# MCU025A_F280049C_Device.net
KiCad netlist of a schematic drawn in Altium Designer
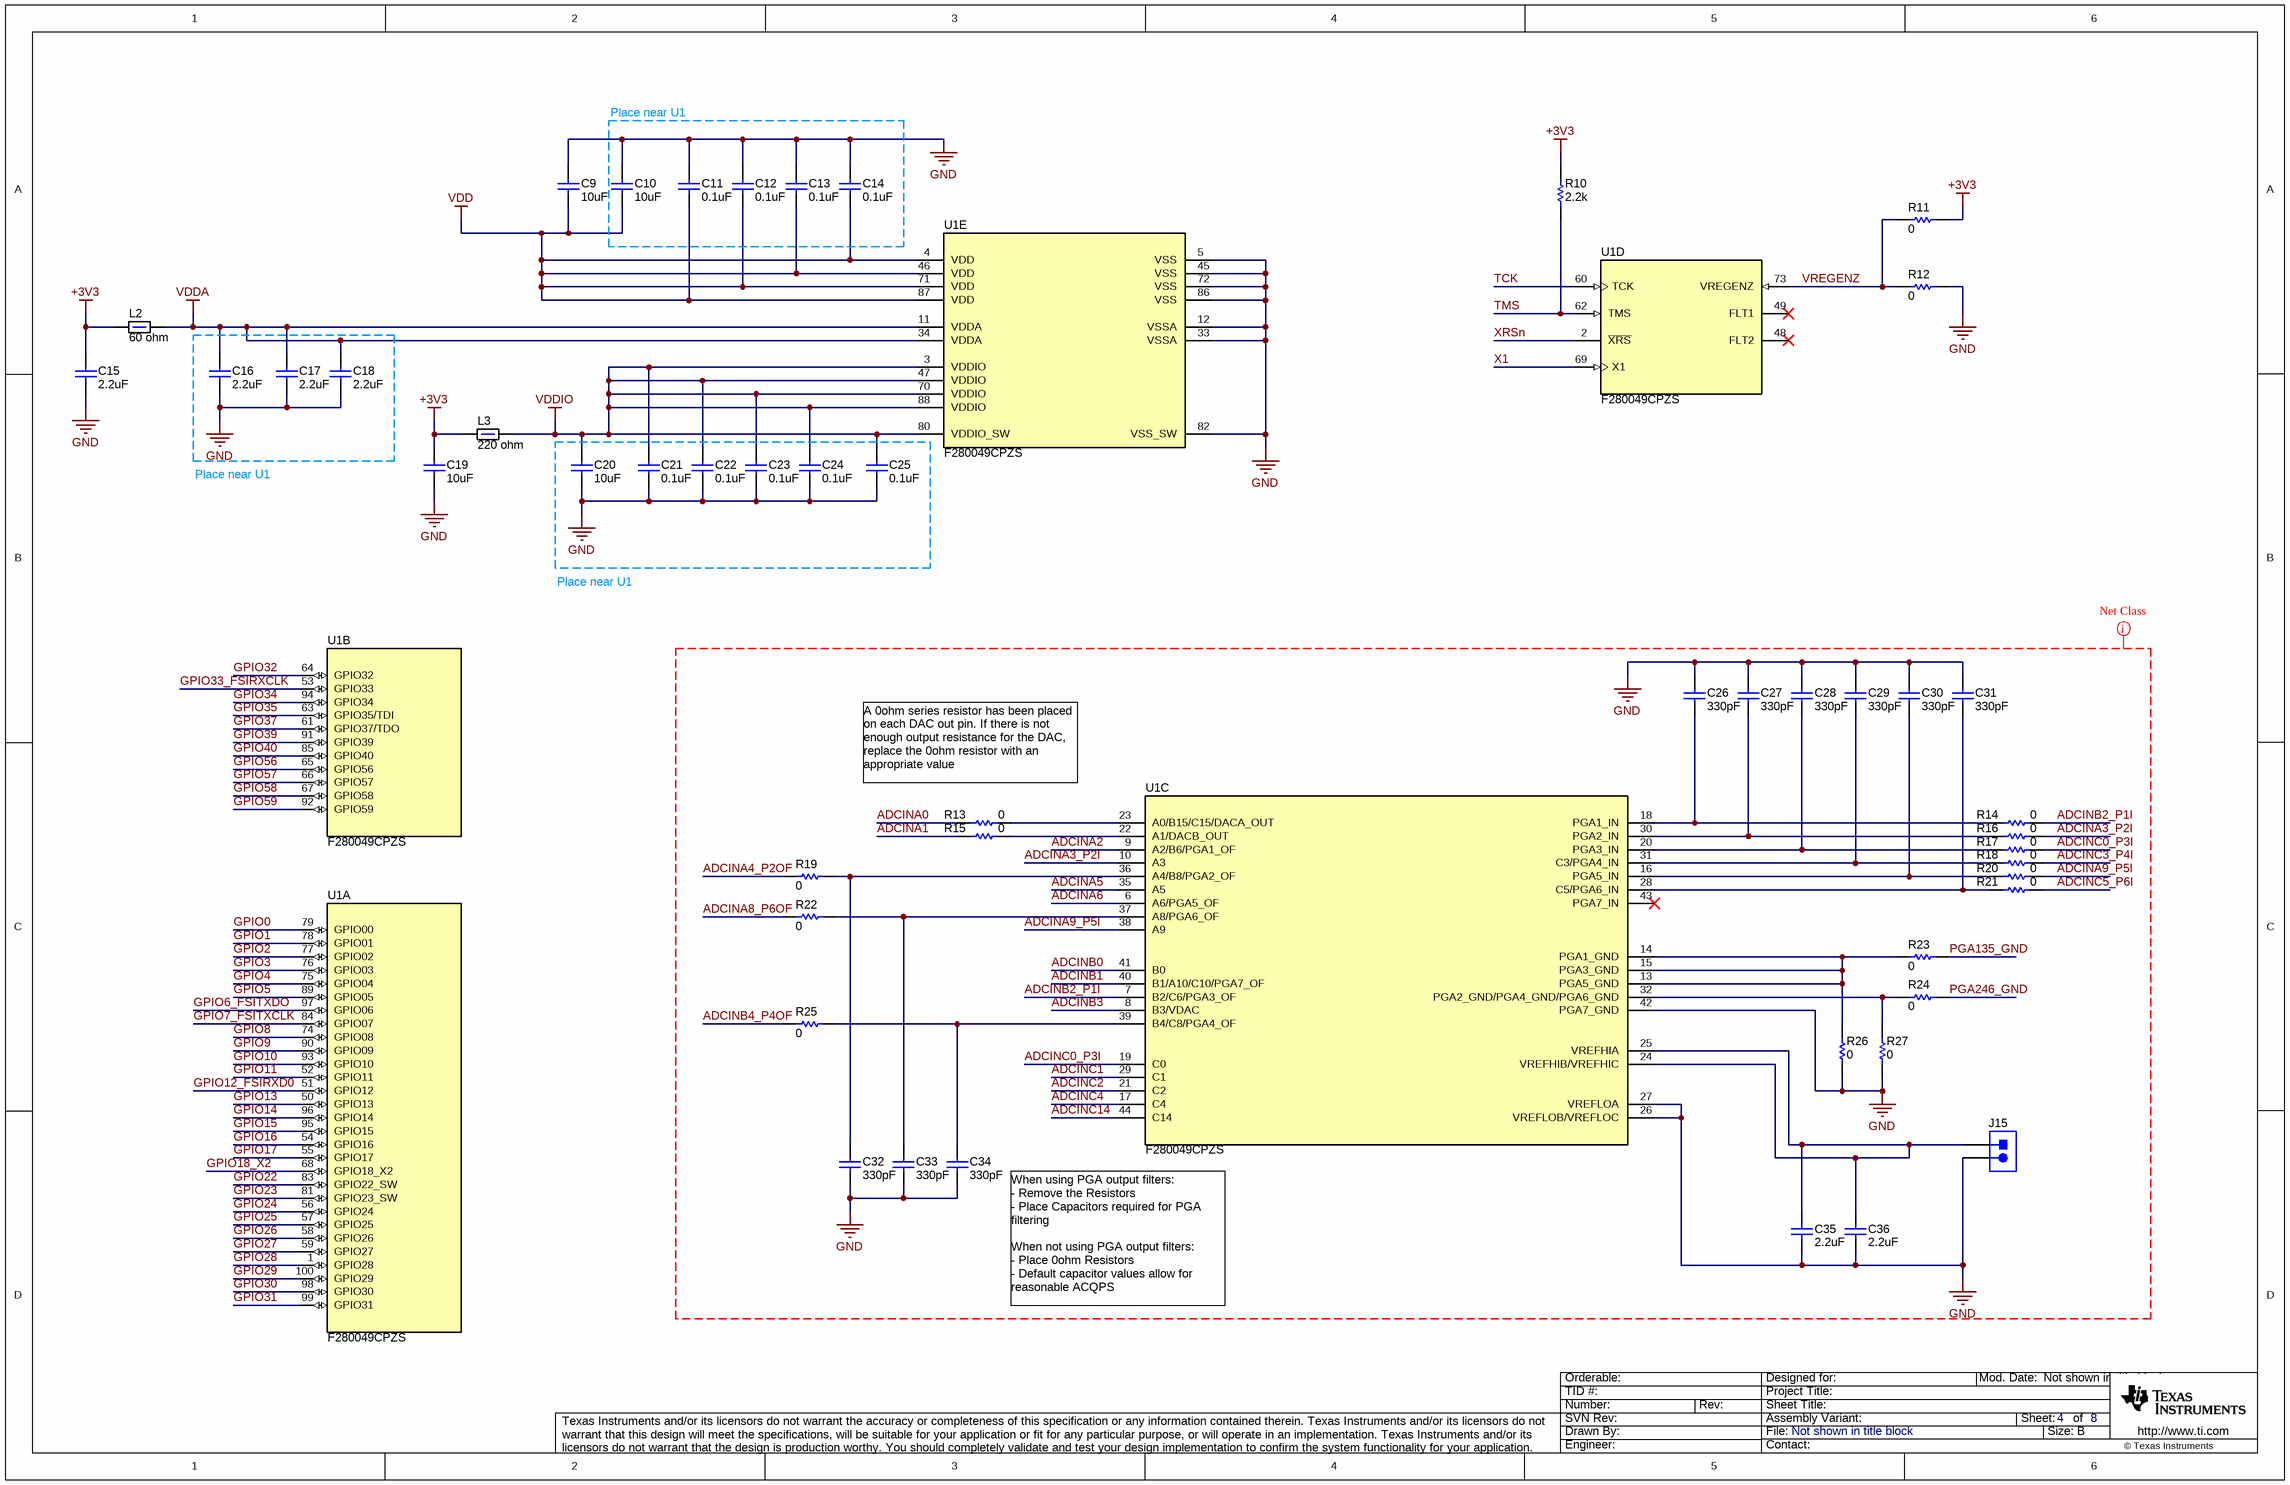
[diagram p0: MCU025A_F280049C_Device.SchDoc]

(export (version "E")
  (design (tool "Eeschema 10.0.6"))
  (components
    (comp (ref "C9")
      (value "GRM188R61A106ME69D")
      (footprint "0603")
      (description "CAP, CERM, 10 uF, 10 V, +/- 20%, X5R, 0603")
      (fields
        (field (name "VALUEDISPLAYED") "10uF")
        (field (name "MANUFACTURER") "MuRata")
        (field (name "PUBLISHER") "Texas Instruments")
      )
      (libsource (lib "Altium Vault - TI") (part "Capacitor"))
    )
    (comp (ref "C10")
      (value "GRM188R61A106ME69D")
      (footprint "0603")
      (description "CAP, CERM, 10 uF, 10 V, +/- 20%, X5R, 0603")
      (fields
        (field (name "VALUEDISPLAYED") "10uF")
        (field (name "MANUFACTURER") "MuRata")
        (field (name "PUBLISHER") "Texas Instruments")
      )
      (libsource (lib "Altium Vault - TI") (part "Capacitor"))
    )
    (comp (ref "C11")
      (value "GRM155R71A104KA01D")
      (footprint "0402")
      (description "CAP, CERM, 0.1 uF, 10 V, +/- 10%, X7R, 0402")
      (fields
        (field (name "VALUEDISPLAYED") "0.1uF")
        (field (name "MANUFACTURER") "MuRata")
        (field (name "PUBLISHER") "Texas Instruments")
      )
      (libsource (lib "Altium Vault - TI") (part "Capacitor"))
    )
    (comp (ref "C12")
      (value "GRM155R71A104KA01D")
      (footprint "0402")
      (description "CAP, CERM, 0.1 uF, 10 V, +/- 10%, X7R, 0402")
      (fields
        (field (name "VALUEDISPLAYED") "0.1uF")
        (field (name "MANUFACTURER") "MuRata")
        (field (name "PUBLISHER") "Texas Instruments")
      )
      (libsource (lib "Altium Vault - TI") (part "Capacitor"))
    )
    (comp (ref "C13")
      (value "GRM155R71A104KA01D")
      (footprint "0402")
      (description "CAP, CERM, 0.1 uF, 10 V, +/- 10%, X7R, 0402")
      (fields
        (field (name "VALUEDISPLAYED") "0.1uF")
        (field (name "MANUFACTURER") "MuRata")
        (field (name "PUBLISHER") "Texas Instruments")
      )
      (libsource (lib "Altium Vault - TI") (part "Capacitor"))
    )
    (comp (ref "C14")
      (value "GRM155R71A104KA01D")
      (footprint "0402")
      (description "CAP, CERM, 0.1 uF, 10 V, +/- 10%, X7R, 0402")
      (fields
        (field (name "VALUEDISPLAYED") "0.1uF")
        (field (name "MANUFACTURER") "MuRata")
        (field (name "PUBLISHER") "Texas Instruments")
      )
      (libsource (lib "Altium Vault - TI") (part "Capacitor"))
    )
    (comp (ref "C15")
      (value "GRM188R61A225KE34D")
      (footprint "0603")
      (description "CAP, CERM, 2.2 uF, 10 V, +/- 10%, X5R, 0603")
      (fields
        (field (name "VALUEDISPLAYED") "2.2uF")
        (field (name "MANUFACTURER") "MuRata")
        (field (name "PUBLISHER") "Texas Instruments")
      )
      (libsource (lib "Altium Vault - TI") (part "Capacitor"))
    )
    (comp (ref "C16")
      (value "GRM188R61A225KE34D")
      (footprint "0603")
      (description "CAP, CERM, 2.2 uF, 10 V, +/- 10%, X5R, 0603")
      (fields
        (field (name "VALUEDISPLAYED") "2.2uF")
        (field (name "MANUFACTURER") "MuRata")
        (field (name "PUBLISHER") "Texas Instruments")
      )
      (libsource (lib "Altium Vault - TI") (part "Capacitor"))
    )
    (comp (ref "C17")
      (value "GRM188R61A225KE34D")
      (footprint "0603")
      (description "CAP, CERM, 2.2 uF, 10 V, +/- 10%, X5R, 0603")
      (fields
        (field (name "VALUEDISPLAYED") "2.2uF")
        (field (name "MANUFACTURER") "MuRata")
        (field (name "PUBLISHER") "Texas Instruments")
      )
      (libsource (lib "Altium Vault - TI") (part "Capacitor"))
    )
    (comp (ref "C18")
      (value "GRM188R61A225KE34D")
      (footprint "0603")
      (description "CAP, CERM, 2.2 uF, 10 V, +/- 10%, X5R, 0603")
      (fields
        (field (name "VALUEDISPLAYED") "2.2uF")
        (field (name "MANUFACTURER") "MuRata")
        (field (name "PUBLISHER") "Texas Instruments")
      )
      (libsource (lib "Altium Vault - TI") (part "Capacitor"))
    )
    (comp (ref "C19")
      (value "GRM188R61A106ME69D")
      (footprint "0603")
      (description "CAP, CERM, 10 uF, 10 V, +/- 20%, X5R, 0603")
      (fields
        (field (name "VALUEDISPLAYED") "10uF")
        (field (name "MANUFACTURER") "MuRata")
        (field (name "PUBLISHER") "Texas Instruments")
      )
      (libsource (lib "Altium Vault - TI") (part "Capacitor"))
    )
    (comp (ref "C20")
      (value "GRM188R61A106ME69D")
      (footprint "0603")
      (description "CAP, CERM, 10 uF, 10 V, +/- 20%, X5R, 0603")
      (fields
        (field (name "VALUEDISPLAYED") "10uF")
        (field (name "MANUFACTURER") "MuRata")
        (field (name "PUBLISHER") "Texas Instruments")
      )
      (libsource (lib "Altium Vault - TI") (part "Capacitor"))
    )
    (comp (ref "C21")
      (value "GRM155R71A104KA01D")
      (footprint "0402")
      (description "CAP, CERM, 0.1 uF, 10 V, +/- 10%, X7R, 0402")
      (fields
        (field (name "VALUEDISPLAYED") "0.1uF")
        (field (name "MANUFACTURER") "MuRata")
        (field (name "PUBLISHER") "Texas Instruments")
      )
      (libsource (lib "Altium Vault - TI") (part "Capacitor"))
    )
    (comp (ref "C22")
      (value "GRM155R71A104KA01D")
      (footprint "0402")
      (description "CAP, CERM, 0.1 uF, 10 V, +/- 10%, X7R, 0402")
      (fields
        (field (name "VALUEDISPLAYED") "0.1uF")
        (field (name "MANUFACTURER") "MuRata")
        (field (name "PUBLISHER") "Texas Instruments")
      )
      (libsource (lib "Altium Vault - TI") (part "Capacitor"))
    )
    (comp (ref "C23")
      (value "GRM155R71A104KA01D")
      (footprint "0402")
      (description "CAP, CERM, 0.1 uF, 10 V, +/- 10%, X7R, 0402")
      (fields
        (field (name "VALUEDISPLAYED") "0.1uF")
        (field (name "MANUFACTURER") "MuRata")
        (field (name "PUBLISHER") "Texas Instruments")
      )
      (libsource (lib "Altium Vault - TI") (part "Capacitor"))
    )
    (comp (ref "C24")
      (value "GRM155R71A104KA01D")
      (footprint "0402")
      (description "CAP, CERM, 0.1 uF, 10 V, +/- 10%, X7R, 0402")
      (fields
        (field (name "VALUEDISPLAYED") "0.1uF")
        (field (name "MANUFACTURER") "MuRata")
        (field (name "PUBLISHER") "Texas Instruments")
      )
      (libsource (lib "Altium Vault - TI") (part "Capacitor"))
    )
    (comp (ref "C25")
      (value "GRM155R71A104KA01D")
      (footprint "0402")
      (description "CAP, CERM, 0.1 uF, 10 V, +/- 10%, X7R, 0402")
      (fields
        (field (name "VALUEDISPLAYED") "0.1uF")
        (field (name "MANUFACTURER") "MuRata")
        (field (name "PUBLISHER") "Texas Instruments")
      )
      (libsource (lib "Altium Vault - TI") (part "Capacitor"))
    )
    (comp (ref "C26")
      (value "GRM1885C1H331JA01D")
      (footprint "0603")
      (description "CAP, CERM, 330 pF, 50 V, +/- 5%, C0G/NP0, 0603")
      (fields
        (field (name "VALUEDISPLAYED") "330pF")
        (field (name "MANUFACTURER") "MuRata")
        (field (name "PUBLISHER") "Texas Instruments")
      )
      (libsource (lib "Altium Vault - TI") (part "Capacitor"))
    )
    (comp (ref "C27")
      (value "GRM1885C1H331JA01D")
      (footprint "0603")
      (description "CAP, CERM, 330 pF, 50 V, +/- 5%, C0G/NP0, 0603")
      (fields
        (field (name "VALUEDISPLAYED") "330pF")
        (field (name "MANUFACTURER") "MuRata")
        (field (name "PUBLISHER") "Texas Instruments")
      )
      (libsource (lib "Altium Vault - TI") (part "Capacitor"))
    )
    (comp (ref "C28")
      (value "GRM1885C1H331JA01D")
      (footprint "0603")
      (description "CAP, CERM, 330 pF, 50 V, +/- 5%, C0G/NP0, 0603")
      (fields
        (field (name "VALUEDISPLAYED") "330pF")
        (field (name "MANUFACTURER") "MuRata")
        (field (name "PUBLISHER") "Texas Instruments")
      )
      (libsource (lib "Altium Vault - TI") (part "Capacitor"))
    )
    (comp (ref "C29")
      (value "GRM1885C1H331JA01D")
      (footprint "0603")
      (description "CAP, CERM, 330 pF, 50 V, +/- 5%, C0G/NP0, 0603")
      (fields
        (field (name "VALUEDISPLAYED") "330pF")
        (field (name "MANUFACTURER") "MuRata")
        (field (name "PUBLISHER") "Texas Instruments")
      )
      (libsource (lib "Altium Vault - TI") (part "Capacitor"))
    )
    (comp (ref "C30")
      (value "GRM1885C1H331JA01D")
      (footprint "0603")
      (description "CAP, CERM, 330 pF, 50 V, +/- 5%, C0G/NP0, 0603")
      (fields
        (field (name "VALUEDISPLAYED") "330pF")
        (field (name "MANUFACTURER") "MuRata")
        (field (name "PUBLISHER") "Texas Instruments")
      )
      (libsource (lib "Altium Vault - TI") (part "Capacitor"))
    )
    (comp (ref "C31")
      (value "GRM1885C1H331JA01D")
      (footprint "0603")
      (description "CAP, CERM, 330 pF, 50 V, +/- 5%, C0G/NP0, 0603")
      (fields
        (field (name "VALUEDISPLAYED") "330pF")
        (field (name "MANUFACTURER") "MuRata")
        (field (name "PUBLISHER") "Texas Instruments")
      )
      (libsource (lib "Altium Vault - TI") (part "Capacitor"))
    )
    (comp (ref "C32")
      (value "GRM1885C1H331JA01D")
      (footprint "0603")
      (description "CAP, CERM, 330 pF, 50 V, +/- 5%, C0G/NP0, 0603")
      (fields
        (field (name "VALUEDISPLAYED") "330pF")
        (field (name "MANUFACTURER") "MuRata")
        (field (name "PUBLISHER") "Texas Instruments")
      )
      (libsource (lib "Altium Vault - TI") (part "Capacitor"))
    )
    (comp (ref "C33")
      (value "GRM1885C1H331JA01D")
      (footprint "0603")
      (description "CAP, CERM, 330 pF, 50 V, +/- 5%, C0G/NP0, 0603")
      (fields
        (field (name "VALUEDISPLAYED") "330pF")
        (field (name "MANUFACTURER") "MuRata")
        (field (name "PUBLISHER") "Texas Instruments")
      )
      (libsource (lib "Altium Vault - TI") (part "Capacitor"))
    )
    (comp (ref "C34")
      (value "GRM1885C1H331JA01D")
      (footprint "0603")
      (description "CAP, CERM, 330 pF, 50 V, +/- 5%, C0G/NP0, 0603")
      (fields
        (field (name "VALUEDISPLAYED") "330pF")
        (field (name "MANUFACTURER") "MuRata")
        (field (name "PUBLISHER") "Texas Instruments")
      )
      (libsource (lib "Altium Vault - TI") (part "Capacitor"))
    )
    (comp (ref "C35")
      (value "GRM188R61A225KE34D")
      (footprint "0603")
      (description "CAP, CERM, 2.2 uF, 10 V, +/- 10%, X5R, 0603")
      (fields
        (field (name "VALUEDISPLAYED") "2.2uF")
        (field (name "MANUFACTURER") "MuRata")
        (field (name "PUBLISHER") "Texas Instruments")
      )
      (libsource (lib "Altium Vault - TI") (part "Capacitor"))
    )
    (comp (ref "C36")
      (value "GRM188R61A225KE34D")
      (footprint "0603")
      (description "CAP, CERM, 2.2 uF, 10 V, +/- 10%, X5R, 0603")
      (fields
        (field (name "VALUEDISPLAYED") "2.2uF")
        (field (name "MANUFACTURER") "MuRata")
        (field (name "PUBLISHER") "Texas Instruments")
      )
      (libsource (lib "Altium Vault - TI") (part "Capacitor"))
    )
    (comp (ref "J15")
      (value "61300211121")
      (footprint "WURTH_61300211121")
      (description "Header, 2.54 mm, 2x1, Gold, TH")
      (fields (field (name "MANUFACTURER") "Wurth Elektronik") (field (name "PUBLISHER") "Texas Instruments"))
      (libsource (lib "Altium Vault - TI") (part "CMP-0054794-1"))
    )
    (comp (ref "L2")
      (value "BKP2125HS600-T")
      (footprint "0805")
      (description "Ferrite Bead, 60 ohm @ 100 MHz, 3 A, 0805")
      (fields
        (field (name "VALUEDISPLAYED") "60 ohm")
        (field (name "MANUFACTURER") "Taiyo Yuden")
        (field (name "PUBLISHER") "Texas Instruments")
      )
      (libsource (lib "Altium Vault - TI") (part "Ferrite_Bead"))
    )
    (comp (ref "L3")
      (value "BLM21PG221SN1D")
      (footprint "0805")
      (description "Ferrite Bead, 220 ohm @ 100 MHz, 2 A, 0805")
      (fields
        (field (name "VALUEDISPLAYED") "220 ohm")
        (field (name "MANUFACTURER") "MuRata")
        (field (name "PUBLISHER") "Texas Instruments")
      )
      (libsource (lib "Altium Vault - TI") (part "Ferrite_Bead"))
    )
    (comp (ref "R10")
      (value "CRCW04022K20JNED")
      (footprint "0402")
      (description "RES, 2.2 k, 5%, 0.063 W, AEC-Q200 Grade 0, 0402")
      (fields (field (name "VALUEDISPLAYED") "2.2k") (field (name "MANUFACTURER") "Vishay-Dale"))
      (libsource (lib "Altium Vault - TI") (part "Resistor"))
    )
    (comp (ref "R11")
      (value "CRCW06030000Z0EA")
      (footprint "0603")
      (description "RES, 0, 5%, 0.1 W, AEC-Q200 Grade 0, 0603")
      (fields (field (name "VALUEDISPLAYED") "0") (field (name "MANUFACTURER") "Vishay-Dale"))
      (libsource (lib "Altium Vault - TI") (part "Resistor"))
    )
    (comp (ref "R12")
      (value "CRCW06030000Z0EA")
      (footprint "0603")
      (description "RES, 0, 5%, 0.1 W, AEC-Q200 Grade 0, 0603")
      (fields (field (name "VALUEDISPLAYED") "0") (field (name "MANUFACTURER") "Vishay-Dale"))
      (libsource (lib "Altium Vault - TI") (part "Resistor"))
    )
    (comp (ref "R13")
      (value "CRCW06030000Z0EA")
      (footprint "0603")
      (description "RES, 0, 5%, 0.1 W, AEC-Q200 Grade 0, 0603")
      (fields (field (name "VALUEDISPLAYED") "0") (field (name "MANUFACTURER") "Vishay-Dale"))
      (libsource (lib "Altium Vault - TI") (part "Resistor"))
    )
    (comp (ref "R14")
      (value "CRCW06030000Z0EA")
      (footprint "0603")
      (description "RES, 0, 5%, 0.1 W, AEC-Q200 Grade 0, 0603")
      (fields (field (name "VALUEDISPLAYED") "0") (field (name "MANUFACTURER") "Vishay-Dale"))
      (libsource (lib "Altium Vault - TI") (part "Resistor"))
    )
    (comp (ref "R15")
      (value "CRCW06030000Z0EA")
      (footprint "0603")
      (description "RES, 0, 5%, 0.1 W, AEC-Q200 Grade 0, 0603")
      (fields (field (name "VALUEDISPLAYED") "0") (field (name "MANUFACTURER") "Vishay-Dale"))
      (libsource (lib "Altium Vault - TI") (part "Resistor"))
    )
    (comp (ref "R16")
      (value "CRCW06030000Z0EA")
      (footprint "0603")
      (description "RES, 0, 5%, 0.1 W, AEC-Q200 Grade 0, 0603")
      (fields (field (name "VALUEDISPLAYED") "0") (field (name "MANUFACTURER") "Vishay-Dale"))
      (libsource (lib "Altium Vault - TI") (part "Resistor"))
    )
    (comp (ref "R17")
      (value "CRCW06030000Z0EA")
      (footprint "0603")
      (description "RES, 0, 5%, 0.1 W, AEC-Q200 Grade 0, 0603")
      (fields (field (name "VALUEDISPLAYED") "0") (field (name "MANUFACTURER") "Vishay-Dale"))
      (libsource (lib "Altium Vault - TI") (part "Resistor"))
    )
    (comp (ref "R18")
      (value "CRCW06030000Z0EA")
      (footprint "0603")
      (description "RES, 0, 5%, 0.1 W, AEC-Q200 Grade 0, 0603")
      (fields (field (name "VALUEDISPLAYED") "0") (field (name "MANUFACTURER") "Vishay-Dale"))
      (libsource (lib "Altium Vault - TI") (part "Resistor"))
    )
    (comp (ref "R19")
      (value "CRCW06030000Z0EA")
      (footprint "0603")
      (description "RES, 0, 5%, 0.1 W, AEC-Q200 Grade 0, 0603")
      (fields (field (name "VALUEDISPLAYED") "0") (field (name "MANUFACTURER") "Vishay-Dale"))
      (libsource (lib "Altium Vault - TI") (part "Resistor"))
    )
    (comp (ref "R20")
      (value "CRCW06030000Z0EA")
      (footprint "0603")
      (description "RES, 0, 5%, 0.1 W, AEC-Q200 Grade 0, 0603")
      (fields (field (name "VALUEDISPLAYED") "0") (field (name "MANUFACTURER") "Vishay-Dale"))
      (libsource (lib "Altium Vault - TI") (part "Resistor"))
    )
    (comp (ref "R21")
      (value "CRCW06030000Z0EA")
      (footprint "0603")
      (description "RES, 0, 5%, 0.1 W, AEC-Q200 Grade 0, 0603")
      (fields (field (name "VALUEDISPLAYED") "0") (field (name "MANUFACTURER") "Vishay-Dale"))
      (libsource (lib "Altium Vault - TI") (part "Resistor"))
    )
    (comp (ref "R22")
      (value "CRCW06030000Z0EA")
      (footprint "0603")
      (description "RES, 0, 5%, 0.1 W, AEC-Q200 Grade 0, 0603")
      (fields (field (name "VALUEDISPLAYED") "0") (field (name "MANUFACTURER") "Vishay-Dale"))
      (libsource (lib "Altium Vault - TI") (part "Resistor"))
    )
    (comp (ref "R23")
      (value "CRCW06030000Z0EA")
      (footprint "0603")
      (description "RES, 0, 5%, 0.1 W, AEC-Q200 Grade 0, 0603")
      (fields (field (name "VALUEDISPLAYED") "0") (field (name "MANUFACTURER") "Vishay-Dale"))
      (libsource (lib "Altium Vault - TI") (part "Resistor"))
    )
    (comp (ref "R24")
      (value "CRCW06030000Z0EA")
      (footprint "0603")
      (description "RES, 0, 5%, 0.1 W, AEC-Q200 Grade 0, 0603")
      (fields (field (name "VALUEDISPLAYED") "0") (field (name "MANUFACTURER") "Vishay-Dale"))
      (libsource (lib "Altium Vault - TI") (part "Resistor"))
    )
    (comp (ref "R25")
      (value "CRCW06030000Z0EA")
      (footprint "0603")
      (description "RES, 0, 5%, 0.1 W, AEC-Q200 Grade 0, 0603")
      (fields (field (name "VALUEDISPLAYED") "0") (field (name "MANUFACTURER") "Vishay-Dale"))
      (libsource (lib "Altium Vault - TI") (part "Resistor"))
    )
    (comp (ref "R26")
      (value "CRCW06030000Z0EA")
      (footprint "0603")
      (description "RES, 0, 5%, 0.1 W, AEC-Q200 Grade 0, 0603")
      (fields (field (name "VALUEDISPLAYED") "0") (field (name "MANUFACTURER") "Vishay-Dale"))
      (libsource (lib "Altium Vault - TI") (part "Resistor"))
    )
    (comp (ref "R27")
      (value "CRCW06030000Z0EA")
      (footprint "0603")
      (description "RES, 0, 5%, 0.1 W, AEC-Q200 Grade 0, 0603")
      (fields (field (name "VALUEDISPLAYED") "0") (field (name "MANUFACTURER") "Vishay-Dale"))
      (libsource (lib "Altium Vault - TI") (part "Resistor"))
    )
    (comp (ref "U1")
      (value "F280049CPZS")
      (footprint "PZ0100A_N")
      (description "Piccolo Microcontroller, PZ0100A (LQFP-100)")
      (fields (field (name "PARTNUMBER") "F280049CPZS") (field (name "MANUFACTURER") "Texas Instruments"))
      (libsource (lib "Altium Vault - TI") (part "F280049PZ"))
    )
  )
  (nets
    (net (code "1") (name "+3V3") (class "Default")
      (node (ref "C15") (pin "1") (pinfunction "1_1") (pintype "passive"))
      (node (ref "C19") (pin "1") (pinfunction "1_1") (pintype "passive"))
      (node (ref "L2") (pin "1") (pinfunction "1_1") (pintype "passive"))
      (node (ref "L3") (pin "1") (pinfunction "1_1") (pintype "passive"))
      (node (ref "R10") (pin "2") (pinfunction "2_2") (pintype "passive"))
      (node (ref "R11") (pin "2") (pinfunction "2_2") (pintype "passive"))
    )
    (net (code "2") (name "/ADCINA0") (class "Default")
      (node (ref "R13") (pin "1") (pinfunction "1_1") (pintype "passive"))
    )
    (net (code "3") (name "/ADCINA1") (class "Default")
      (node (ref "R15") (pin "1") (pinfunction "1_1") (pintype "passive"))
    )
    (net (code "4") (name "/ADCINA2") (class "Default")
      (node (ref "U1") (pin "9") (pinfunction "A2/B6/PGA1_OF_9") (pintype "passive"))
    )
    (net (code "5") (name "/ADCINA3_P2I") (class "Default")
      (node (ref "R16") (pin "2") (pinfunction "2_2") (pintype "passive"))
      (node (ref "U1") (pin "10") (pinfunction "A3_10") (pintype "passive"))
    )
    (net (code "6") (name "/ADCINA4_P2OF") (class "Default")
      (node (ref "R19") (pin "1") (pinfunction "1_1") (pintype "passive"))
    )
    (net (code "7") (name "/ADCINA5") (class "Default")
      (node (ref "U1") (pin "35") (pinfunction "A5_35") (pintype "passive"))
    )
    (net (code "8") (name "/ADCINA6") (class "Default")
      (node (ref "U1") (pin "6") (pinfunction "A6/PGA5_OF_6") (pintype "passive"))
    )
    (net (code "9") (name "/ADCINA8_P6OF") (class "Default")
      (node (ref "R22") (pin "1") (pinfunction "1_1") (pintype "passive"))
    )
    (net (code "10") (name "/ADCINA9_P5I") (class "Default")
      (node (ref "R20") (pin "2") (pinfunction "2_2") (pintype "passive"))
      (node (ref "U1") (pin "38") (pinfunction "A9_38") (pintype "passive"))
    )
    (net (code "11") (name "/ADCINB0") (class "Default")
      (node (ref "U1") (pin "41") (pinfunction "B0_41") (pintype "passive"))
    )
    (net (code "12") (name "/ADCINB1") (class "Default")
      (node (ref "U1") (pin "40") (pinfunction "B1/A10/C10/PGA7_OF_40") (pintype "passive"))
    )
    (net (code "13") (name "/ADCINB2_P1I") (class "Default")
      (node (ref "R14") (pin "2") (pinfunction "2_2") (pintype "passive"))
      (node (ref "U1") (pin "7") (pinfunction "B2/C6/PGA3_OF_7") (pintype "passive"))
    )
    (net (code "14") (name "/ADCINB3") (class "Default")
      (node (ref "U1") (pin "8") (pinfunction "B3/VDAC_8") (pintype "passive"))
    )
    (net (code "15") (name "/ADCINB4_P4OF") (class "Default")
      (node (ref "R25") (pin "1") (pinfunction "1_1") (pintype "passive"))
    )
    (net (code "16") (name "/ADCINC0_P3I") (class "Default")
      (node (ref "R17") (pin "2") (pinfunction "2_2") (pintype "passive"))
      (node (ref "U1") (pin "19") (pinfunction "C0_19") (pintype "passive"))
    )
    (net (code "17") (name "/ADCINC1") (class "Default")
      (node (ref "U1") (pin "29") (pinfunction "C1_29") (pintype "passive"))
    )
    (net (code "18") (name "/ADCINC2") (class "Default")
      (node (ref "U1") (pin "21") (pinfunction "C2_21") (pintype "passive"))
    )
    (net (code "19") (name "/ADCINC3_P4I") (class "Default")
      (node (ref "R18") (pin "2") (pinfunction "2_2") (pintype "passive"))
    )
    (net (code "20") (name "/ADCINC4") (class "Default")
      (node (ref "U1") (pin "17") (pinfunction "C4_17") (pintype "passive"))
    )
    (net (code "21") (name "/ADCINC5_P6I") (class "Default")
      (node (ref "R21") (pin "2") (pinfunction "2_2") (pintype "passive"))
    )
    (net (code "22") (name "/ADCINC14") (class "Default")
      (node (ref "U1") (pin "44") (pinfunction "C14_44") (pintype "passive"))
    )
    (net (code "23") (name "/GPIO0") (class "Default")
      (node (ref "U1") (pin "79") (pinfunction "GPIO00_79") (pintype "bidirectional"))
    )
    (net (code "24") (name "/GPIO1") (class "Default")
      (node (ref "U1") (pin "78") (pinfunction "GPIO01_78") (pintype "bidirectional"))
    )
    (net (code "25") (name "/GPIO2") (class "Default")
      (node (ref "U1") (pin "77") (pinfunction "GPIO02_77") (pintype "bidirectional"))
    )
    (net (code "26") (name "/GPIO3") (class "Default")
      (node (ref "U1") (pin "76") (pinfunction "GPIO03_76") (pintype "bidirectional"))
    )
    (net (code "27") (name "/GPIO4") (class "Default")
      (node (ref "U1") (pin "75") (pinfunction "GPIO04_75") (pintype "bidirectional"))
    )
    (net (code "28") (name "/GPIO5") (class "Default")
      (node (ref "U1") (pin "89") (pinfunction "GPIO05_89") (pintype "bidirectional"))
    )
    (net (code "29") (name "/GPIO6_FSITXDO") (class "Default")
      (node (ref "U1") (pin "97") (pinfunction "GPIO06_97") (pintype "bidirectional"))
    )
    (net (code "30") (name "/GPIO7_FSITXCLK") (class "Default")
      (node (ref "U1") (pin "84") (pinfunction "GPIO07_84") (pintype "bidirectional"))
    )
    (net (code "31") (name "/GPIO8") (class "Default")
      (node (ref "U1") (pin "74") (pinfunction "GPIO08_74") (pintype "bidirectional"))
    )
    (net (code "32") (name "/GPIO9") (class "Default")
      (node (ref "U1") (pin "90") (pinfunction "GPIO09_90") (pintype "bidirectional"))
    )
    (net (code "33") (name "/GPIO10") (class "Default")
      (node (ref "U1") (pin "93") (pinfunction "GPIO10_93") (pintype "bidirectional"))
    )
    (net (code "34") (name "/GPIO11") (class "Default")
      (node (ref "U1") (pin "52") (pinfunction "GPIO11_52") (pintype "bidirectional"))
    )
    (net (code "35") (name "/GPIO12_FSIRXD0") (class "Default")
      (node (ref "U1") (pin "51") (pinfunction "GPIO12_51") (pintype "bidirectional"))
    )
    (net (code "36") (name "/GPIO13") (class "Default")
      (node (ref "U1") (pin "50") (pinfunction "GPIO13_50") (pintype "bidirectional"))
    )
    (net (code "37") (name "/GPIO14") (class "Default")
      (node (ref "U1") (pin "96") (pinfunction "GPIO14_96") (pintype "bidirectional"))
    )
    (net (code "38") (name "/GPIO15") (class "Default")
      (node (ref "U1") (pin "95") (pinfunction "GPIO15_95") (pintype "bidirectional"))
    )
    (net (code "39") (name "/GPIO16") (class "Default")
      (node (ref "U1") (pin "54") (pinfunction "GPIO16_54") (pintype "bidirectional"))
    )
    (net (code "40") (name "/GPIO17") (class "Default")
      (node (ref "U1") (pin "55") (pinfunction "GPIO17_55") (pintype "bidirectional"))
    )
    (net (code "41") (name "/GPIO18_X2") (class "Default")
      (node (ref "U1") (pin "68") (pinfunction "GPIO18_X2_68") (pintype "bidirectional"))
    )
    (net (code "42") (name "/GPIO22") (class "Default")
      (node (ref "U1") (pin "83") (pinfunction "GPIO22_SW_83") (pintype "bidirectional"))
    )
    (net (code "43") (name "/GPIO23") (class "Default")
      (node (ref "U1") (pin "81") (pinfunction "GPIO23_SW_81") (pintype "bidirectional"))
    )
    (net (code "44") (name "/GPIO24") (class "Default")
      (node (ref "U1") (pin "56") (pinfunction "GPIO24_56") (pintype "bidirectional"))
    )
    (net (code "45") (name "/GPIO25") (class "Default")
      (node (ref "U1") (pin "57") (pinfunction "GPIO25_57") (pintype "bidirectional"))
    )
    (net (code "46") (name "/GPIO26") (class "Default")
      (node (ref "U1") (pin "58") (pinfunction "GPIO26_58") (pintype "bidirectional"))
    )
    (net (code "47") (name "/GPIO27") (class "Default")
      (node (ref "U1") (pin "59") (pinfunction "GPIO27_59") (pintype "bidirectional"))
    )
    (net (code "48") (name "/GPIO28") (class "Default")
      (node (ref "U1") (pin "1") (pinfunction "GPIO28_1") (pintype "bidirectional"))
    )
    (net (code "49") (name "/GPIO29") (class "Default")
      (node (ref "U1") (pin "100") (pinfunction "GPIO29_100") (pintype "bidirectional"))
    )
    (net (code "50") (name "/GPIO30") (class "Default")
      (node (ref "U1") (pin "98") (pinfunction "GPIO30_98") (pintype "bidirectional"))
    )
    (net (code "51") (name "/GPIO31") (class "Default")
      (node (ref "U1") (pin "99") (pinfunction "GPIO31_99") (pintype "bidirectional"))
    )
    (net (code "52") (name "/GPIO32") (class "Default")
      (node (ref "U1") (pin "64") (pinfunction "GPIO32_64") (pintype "bidirectional"))
    )
    (net (code "53") (name "/GPIO33_FSIRXCLK") (class "Default")
      (node (ref "U1") (pin "53") (pinfunction "GPIO33_53") (pintype "bidirectional"))
    )
    (net (code "54") (name "/GPIO34") (class "Default")
      (node (ref "U1") (pin "94") (pinfunction "GPIO34_94") (pintype "bidirectional"))
    )
    (net (code "55") (name "/GPIO35") (class "Default")
      (node (ref "U1") (pin "63") (pinfunction "GPIO35/TDI_63") (pintype "bidirectional"))
    )
    (net (code "56") (name "/GPIO37") (class "Default")
      (node (ref "U1") (pin "61") (pinfunction "GPIO37/TDO_61") (pintype "bidirectional"))
    )
    (net (code "57") (name "/GPIO39") (class "Default")
      (node (ref "U1") (pin "91") (pinfunction "GPIO39_91") (pintype "bidirectional"))
    )
    (net (code "58") (name "/GPIO40") (class "Default")
      (node (ref "U1") (pin "85") (pinfunction "GPIO40_85") (pintype "bidirectional"))
    )
    (net (code "59") (name "/GPIO56") (class "Default")
      (node (ref "U1") (pin "65") (pinfunction "GPIO56_65") (pintype "bidirectional"))
    )
    (net (code "60") (name "/GPIO57") (class "Default")
      (node (ref "U1") (pin "66") (pinfunction "GPIO57_66") (pintype "bidirectional"))
    )
    (net (code "61") (name "/GPIO58") (class "Default")
      (node (ref "U1") (pin "67") (pinfunction "GPIO58_67") (pintype "bidirectional"))
    )
    (net (code "62") (name "/GPIO59") (class "Default")
      (node (ref "U1") (pin "92") (pinfunction "GPIO59_92") (pintype "bidirectional"))
    )
    (net (code "63") (name "/PGA135_GND") (class "Default")
      (node (ref "R23") (pin "2") (pinfunction "2_2") (pintype "passive"))
    )
    (net (code "64") (name "/PGA246_GND") (class "Default")
      (node (ref "R24") (pin "2") (pinfunction "2_2") (pintype "passive"))
    )
    (net (code "65") (name "/TCK") (class "Default")
      (node (ref "U1") (pin "60") (pinfunction "TCK_60") (pintype "input"))
    )
    (net (code "66") (name "/TMS") (class "Default")
      (node (ref "R10") (pin "1") (pinfunction "1_1") (pintype "passive"))
      (node (ref "U1") (pin "62") (pinfunction "TMS_62") (pintype "input"))
    )
    (net (code "67") (name "/VREGENZ") (class "Default")
      (node (ref "R11") (pin "1") (pinfunction "1_1") (pintype "passive"))
      (node (ref "R12") (pin "1") (pinfunction "1_1") (pintype "passive"))
      (node (ref "U1") (pin "73") (pinfunction "VREGENZ_73") (pintype "input"))
    )
    (net (code "68") (name "/X1") (class "Default")
      (node (ref "U1") (pin "69") (pinfunction "X1_69") (pintype "input"))
    )
    (net (code "69") (name "/XRSn") (class "Default")
      (node (ref "U1") (pin "2") (pinfunction "XRS_2") (pintype "open_collector"))
    )
    (net (code "70") (name "GND") (class "Default")
      (node (ref "C10") (pin "1") (pinfunction "1_1") (pintype "passive"))
      (node (ref "C11") (pin "2") (pinfunction "2_2") (pintype "passive"))
      (node (ref "C12") (pin "2") (pinfunction "2_2") (pintype "passive"))
      (node (ref "C13") (pin "2") (pinfunction "2_2") (pintype "passive"))
      (node (ref "C14") (pin "2") (pinfunction "2_2") (pintype "passive"))
      (node (ref "C15") (pin "2") (pinfunction "2_2") (pintype "passive"))
      (node (ref "C16") (pin "2") (pinfunction "2_2") (pintype "passive"))
      (node (ref "C17") (pin "2") (pinfunction "2_2") (pintype "passive"))
      (node (ref "C18") (pin "2") (pinfunction "2_2") (pintype "passive"))
      (node (ref "C19") (pin "2") (pinfunction "2_2") (pintype "passive"))
      (node (ref "C20") (pin "2") (pinfunction "2_2") (pintype "passive"))
      (node (ref "C21") (pin "1") (pinfunction "1_1") (pintype "passive"))
      (node (ref "C22") (pin "1") (pinfunction "1_1") (pintype "passive"))
      (node (ref "C23") (pin "1") (pinfunction "1_1") (pintype "passive"))
      (node (ref "C24") (pin "1") (pinfunction "1_1") (pintype "passive"))
      (node (ref "C25") (pin "1") (pinfunction "1_1") (pintype "passive"))
      (node (ref "C26") (pin "1") (pinfunction "1_1") (pintype "passive"))
      (node (ref "C27") (pin "1") (pinfunction "1_1") (pintype "passive"))
      (node (ref "C28") (pin "1") (pinfunction "1_1") (pintype "passive"))
      (node (ref "C29") (pin "1") (pinfunction "1_1") (pintype "passive"))
      (node (ref "C30") (pin "1") (pinfunction "1_1") (pintype "passive"))
      (node (ref "C31") (pin "1") (pinfunction "1_1") (pintype "passive"))
      (node (ref "C32") (pin "2") (pinfunction "2_2") (pintype "passive"))
      (node (ref "C33") (pin "2") (pinfunction "2_2") (pintype "passive"))
      (node (ref "C34") (pin "2") (pinfunction "2_2") (pintype "passive"))
      (node (ref "C35") (pin "2") (pinfunction "2_2") (pintype "passive"))
      (node (ref "C36") (pin "2") (pinfunction "2_2") (pintype "passive"))
      (node (ref "C9") (pin "1") (pinfunction "1_1") (pintype "passive"))
      (node (ref "J15") (pin "2") (pinfunction "2_2") (pintype "passive"))
      (node (ref "R12") (pin "2") (pinfunction "2_2") (pintype "passive"))
      (node (ref "R26") (pin "1") (pinfunction "1_1") (pintype "passive"))
      (node (ref "R27") (pin "1") (pinfunction "1_1") (pintype "passive"))
      (node (ref "U1") (pin "12") (pinfunction "VSSA_12") (pintype "power_in"))
      (node (ref "U1") (pin "26") (pinfunction "VREFLOB/VREFLOC_26") (pintype "passive"))
      (node (ref "U1") (pin "27") (pinfunction "VREFLOA_27") (pintype "passive"))
      (node (ref "U1") (pin "33") (pinfunction "VSSA_33") (pintype "power_in"))
      (node (ref "U1") (pin "42") (pinfunction "PGA7_GND_42") (pintype "passive"))
      (node (ref "U1") (pin "45") (pinfunction "VSS_45") (pintype "power_in"))
      (node (ref "U1") (pin "5") (pinfunction "VSS_5") (pintype "power_in"))
      (node (ref "U1") (pin "72") (pinfunction "VSS_72") (pintype "power_in"))
      (node (ref "U1") (pin "82") (pinfunction "VSS_SW_82") (pintype "power_in"))
      (node (ref "U1") (pin "86") (pinfunction "VSS_86") (pintype "power_in"))
    )
    (net (code "71") (name "Net-(U1C-A0{slash}B15{slash}C15{slash}DACA_OUT)") (class "Default")
      (node (ref "R13") (pin "2") (pinfunction "2_2") (pintype "passive"))
      (node (ref "U1") (pin "23") (pinfunction "A0/B15/C15/DACA_OUT_23") (pintype "passive"))
    )
    (net (code "72") (name "Net-(U1C-A1{slash}DACB_OUT)") (class "Default")
      (node (ref "R15") (pin "2") (pinfunction "2_2") (pintype "passive"))
      (node (ref "U1") (pin "22") (pinfunction "A1/DACB_OUT_22") (pintype "passive"))
    )
    (net (code "73") (name "Net-(U1C-A4{slash}B8{slash}PGA2_OF)") (class "Default")
      (node (ref "C32") (pin "1") (pinfunction "1_1") (pintype "passive"))
      (node (ref "R19") (pin "2") (pinfunction "2_2") (pintype "passive"))
      (node (ref "U1") (pin "36") (pinfunction "A4/B8/PGA2_OF_36") (pintype "passive"))
    )
    (net (code "74") (name "Net-(U1C-A8{slash}PGA6_OF)") (class "Default")
      (node (ref "C33") (pin "1") (pinfunction "1_1") (pintype "passive"))
      (node (ref "R22") (pin "2") (pinfunction "2_2") (pintype "passive"))
      (node (ref "U1") (pin "37") (pinfunction "A8/PGA6_OF_37") (pintype "passive"))
    )
    (net (code "75") (name "Net-(U1C-B4{slash}C8{slash}PGA4_OF)") (class "Default")
      (node (ref "C34") (pin "1") (pinfunction "1_1") (pintype "passive"))
      (node (ref "R25") (pin "2") (pinfunction "2_2") (pintype "passive"))
      (node (ref "U1") (pin "39") (pinfunction "B4/C8/PGA4_OF_39") (pintype "passive"))
    )
    (net (code "76") (name "Net-(U1C-C3{slash}PGA4_IN)") (class "Default")
      (node (ref "C29") (pin "2") (pinfunction "2_2") (pintype "passive"))
      (node (ref "R18") (pin "1") (pinfunction "1_1") (pintype "passive"))
      (node (ref "U1") (pin "31") (pinfunction "C3/PGA4_IN_31") (pintype "passive"))
    )
    (net (code "77") (name "Net-(U1C-C5{slash}PGA6_IN)") (class "Default")
      (node (ref "C31") (pin "2") (pinfunction "2_2") (pintype "passive"))
      (node (ref "R21") (pin "1") (pinfunction "1_1") (pintype "passive"))
      (node (ref "U1") (pin "28") (pinfunction "C5/PGA6_IN_28") (pintype "passive"))
    )
    (net (code "78") (name "Net-(U1C-PGA1_GND)") (class "Default")
      (node (ref "R23") (pin "1") (pinfunction "1_1") (pintype "passive"))
      (node (ref "R26") (pin "2") (pinfunction "2_2") (pintype "passive"))
      (node (ref "U1") (pin "13") (pinfunction "PGA5_GND_13") (pintype "passive"))
      (node (ref "U1") (pin "14") (pinfunction "PGA1_GND_14") (pintype "passive"))
      (node (ref "U1") (pin "15") (pinfunction "PGA3_GND_15") (pintype "passive"))
    )
    (net (code "79") (name "Net-(U1C-PGA1_IN)") (class "Default")
      (node (ref "C26") (pin "2") (pinfunction "2_2") (pintype "passive"))
      (node (ref "R14") (pin "1") (pinfunction "1_1") (pintype "passive"))
      (node (ref "U1") (pin "18") (pinfunction "PGA1_IN_18") (pintype "passive"))
    )
    (net (code "80") (name "Net-(U1C-PGA2_GND{slash}PGA4_GND{slash}PGA6_GND)") (class "Default")
      (node (ref "R24") (pin "1") (pinfunction "1_1") (pintype "passive"))
      (node (ref "R27") (pin "2") (pinfunction "2_2") (pintype "passive"))
      (node (ref "U1") (pin "32") (pinfunction "PGA2_GND/PGA4_GND/PGA6_GND_32") (pintype "passive"))
    )
    (net (code "81") (name "Net-(U1C-PGA2_IN)") (class "Default")
      (node (ref "C27") (pin "2") (pinfunction "2_2") (pintype "passive"))
      (node (ref "R16") (pin "1") (pinfunction "1_1") (pintype "passive"))
      (node (ref "U1") (pin "30") (pinfunction "PGA2_IN_30") (pintype "passive"))
    )
    (net (code "82") (name "Net-(U1C-PGA3_IN)") (class "Default")
      (node (ref "C28") (pin "2") (pinfunction "2_2") (pintype "passive"))
      (node (ref "R17") (pin "1") (pinfunction "1_1") (pintype "passive"))
      (node (ref "U1") (pin "20") (pinfunction "PGA3_IN_20") (pintype "passive"))
    )
    (net (code "83") (name "Net-(U1C-PGA5_IN)") (class "Default")
      (node (ref "C30") (pin "2") (pinfunction "2_2") (pintype "passive"))
      (node (ref "R20") (pin "1") (pinfunction "1_1") (pintype "passive"))
      (node (ref "U1") (pin "16") (pinfunction "PGA5_IN_16") (pintype "passive"))
    )
    (net (code "84") (name "Net-(U1C-VREFHIA)") (class "Default")
      (node (ref "C35") (pin "1") (pinfunction "1_1") (pintype "passive"))
      (node (ref "C36") (pin "1") (pinfunction "1_1") (pintype "passive"))
      (node (ref "J15") (pin "1") (pinfunction "1_1") (pintype "passive"))
      (node (ref "U1") (pin "24") (pinfunction "VREFHIB/VREFHIC_24") (pintype "passive"))
      (node (ref "U1") (pin "25") (pinfunction "VREFHIA_25") (pintype "passive"))
    )
    (net (code "85") (name "VDD") (class "Default")
      (node (ref "C10") (pin "2") (pinfunction "2_2") (pintype "passive"))
      (node (ref "C11") (pin "1") (pinfunction "1_1") (pintype "passive"))
      (node (ref "C12") (pin "1") (pinfunction "1_1") (pintype "passive"))
      (node (ref "C13") (pin "1") (pinfunction "1_1") (pintype "passive"))
      (node (ref "C14") (pin "1") (pinfunction "1_1") (pintype "passive"))
      (node (ref "C9") (pin "2") (pinfunction "2_2") (pintype "passive"))
      (node (ref "U1") (pin "4") (pinfunction "VDD_4") (pintype "power_in"))
      (node (ref "U1") (pin "46") (pinfunction "VDD_46") (pintype "power_in"))
      (node (ref "U1") (pin "71") (pinfunction "VDD_71") (pintype "power_in"))
      (node (ref "U1") (pin "87") (pinfunction "VDD_87") (pintype "power_in"))
    )
    (net (code "86") (name "VDDA") (class "Default")
      (node (ref "C16") (pin "1") (pinfunction "1_1") (pintype "passive"))
      (node (ref "C17") (pin "1") (pinfunction "1_1") (pintype "passive"))
      (node (ref "C18") (pin "1") (pinfunction "1_1") (pintype "passive"))
      (node (ref "L2") (pin "2") (pinfunction "2_2") (pintype "passive"))
      (node (ref "U1") (pin "11") (pinfunction "VDDA_11") (pintype "power_in"))
      (node (ref "U1") (pin "34") (pinfunction "VDDA_34") (pintype "power_in"))
    )
    (net (code "87") (name "VDDIO") (class "Default")
      (node (ref "C20") (pin "1") (pinfunction "1_1") (pintype "passive"))
      (node (ref "C21") (pin "2") (pinfunction "2_2") (pintype "passive"))
      (node (ref "C22") (pin "2") (pinfunction "2_2") (pintype "passive"))
      (node (ref "C23") (pin "2") (pinfunction "2_2") (pintype "passive"))
      (node (ref "C24") (pin "2") (pinfunction "2_2") (pintype "passive"))
      (node (ref "C25") (pin "2") (pinfunction "2_2") (pintype "passive"))
      (node (ref "L3") (pin "2") (pinfunction "2_2") (pintype "passive"))
      (node (ref "U1") (pin "3") (pinfunction "VDDIO_3") (pintype "power_in"))
      (node (ref "U1") (pin "47") (pinfunction "VDDIO_47") (pintype "power_in"))
      (node (ref "U1") (pin "70") (pinfunction "VDDIO_70") (pintype "power_in"))
      (node (ref "U1") (pin "80") (pinfunction "VDDIO_SW_80") (pintype "power_in"))
      (node (ref "U1") (pin "88") (pinfunction "VDDIO_88") (pintype "power_in"))
    )
    (net (code "88") (name "unconnected-(U1C-PGA7_IN-Pad43)") (class "Default")
      (node (ref "U1") (pin "43") (pinfunction "PGA7_IN_43") (pintype "passive+no_connect"))
    )
    (net (code "89") (name "unconnected-(U1D-FLT1-Pad49)") (class "Default")
      (node (ref "U1") (pin "49") (pinfunction "FLT1_49") (pintype "passive+no_connect"))
    )
    (net (code "90") (name "unconnected-(U1D-FLT2-Pad48)") (class "Default")
      (node (ref "U1") (pin "48") (pinfunction "FLT2_48") (pintype "passive+no_connect"))
    )
  )
)
